# ESP-12.net
KiCad netlist of a schematic drawn in EAGLE
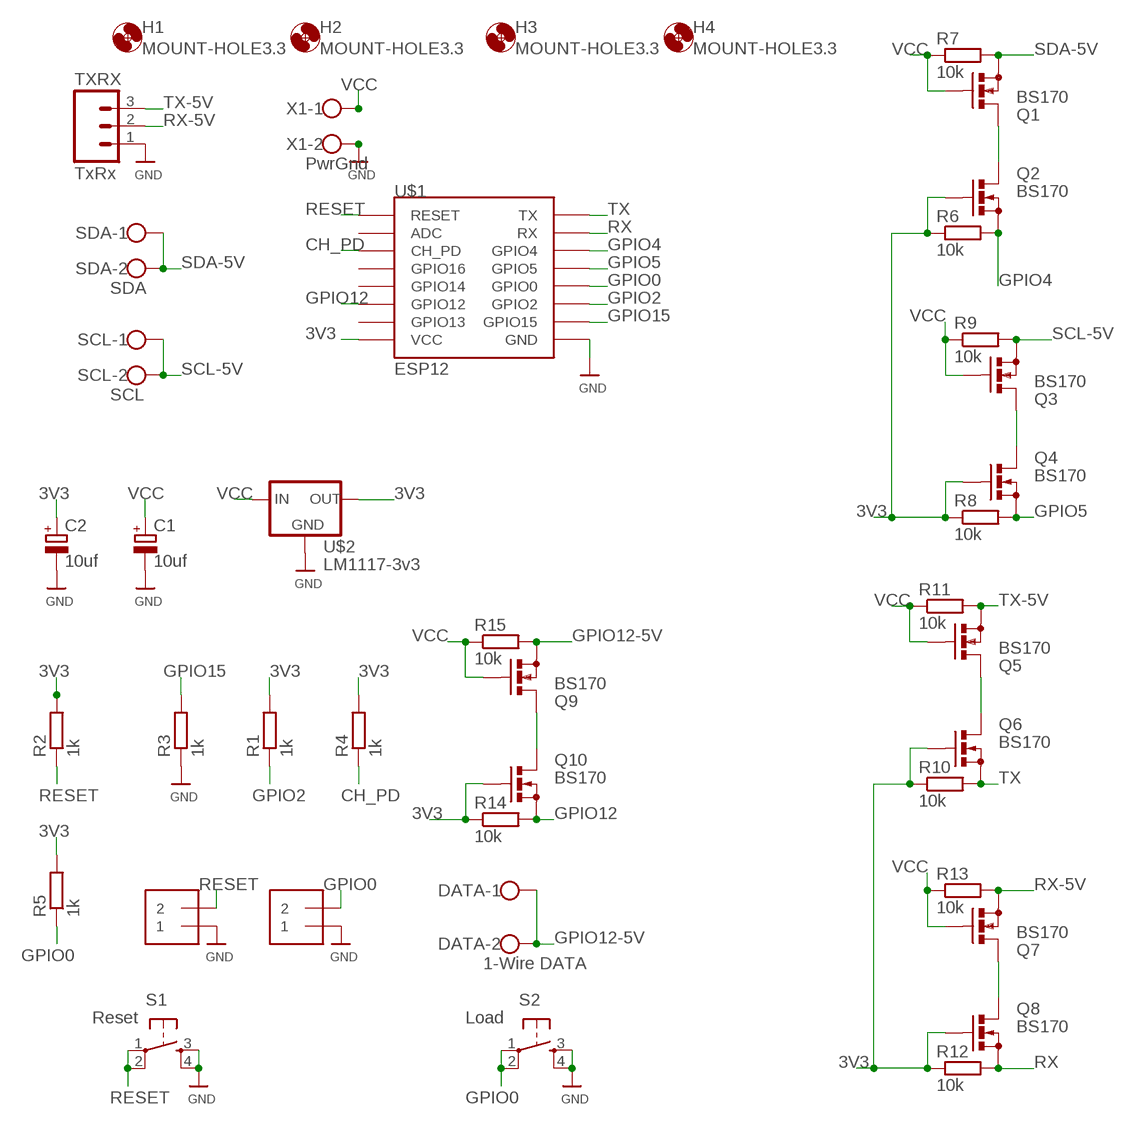
[diagram p0: schematic, sheet 1]

(export (version "E")
  (design (tool "Eeschema 10.0.6"))
  (components
    (comp (ref "C1")
      (value "10uf")
      (footprint "eagle-import:E5-4")
      (libsource (lib "eagle-import") (part "CPOL-EUE5-4"))
    )
    (comp (ref "C2")
      (value "10uf")
      (footprint "eagle-import:E5-4")
      (libsource (lib "eagle-import") (part "CPOL-EUE5-4"))
    )
    (comp (ref "DATA")
      (value "1-Wire DATA")
      (footprint "eagle-import:W237-102")
      (fields (field (name "MPN") "237-102"))
      (libsource (lib "eagle-import") (part "W237-102"))
    )
    (comp (ref "H1")
      (value "MOUNT-HOLE3.3")
      (footprint "eagle-import:3,3")
      (libsource (lib "eagle-import") (part "MOUNT-HOLE3.3"))
    )
    (comp (ref "H2")
      (value "MOUNT-HOLE3.3")
      (footprint "eagle-import:3,3")
      (libsource (lib "eagle-import") (part "MOUNT-HOLE3.3"))
    )
    (comp (ref "H3")
      (value "MOUNT-HOLE3.3")
      (footprint "eagle-import:3,3")
      (libsource (lib "eagle-import") (part "MOUNT-HOLE3.3"))
    )
    (comp (ref "H4")
      (value "MOUNT-HOLE3.3")
      (footprint "eagle-import:3,3")
      (libsource (lib "eagle-import") (part "MOUNT-HOLE3.3"))
    )
    (comp (ref "J1")
      (value "1X2-3.5MM")
      (footprint "eagle-import:1X2-3.5MM")
      (libsource (lib "eagle-import") (part "1X2-3.5MM"))
    )
    (comp (ref "J2")
      (value "1X2-3.5MM")
      (footprint "eagle-import:1X2-3.5MM")
      (libsource (lib "eagle-import") (part "1X2-3.5MM"))
    )
    (comp (ref "Q1")
      (value "BS170")
      (footprint "eagle-import:SOT54E")
      (libsource (lib "eagle-import") (part "BS170"))
    )
    (comp (ref "Q2")
      (value "BS170")
      (footprint "eagle-import:SOT54E")
      (libsource (lib "eagle-import") (part "BS170"))
    )
    (comp (ref "Q3")
      (value "BS170")
      (footprint "eagle-import:SOT54E")
      (libsource (lib "eagle-import") (part "BS170"))
    )
    (comp (ref "Q4")
      (value "BS170")
      (footprint "eagle-import:SOT54E")
      (libsource (lib "eagle-import") (part "BS170"))
    )
    (comp (ref "Q5")
      (value "BS170")
      (footprint "eagle-import:SOT54E")
      (libsource (lib "eagle-import") (part "BS170"))
    )
    (comp (ref "Q6")
      (value "BS170")
      (footprint "eagle-import:SOT54E")
      (libsource (lib "eagle-import") (part "BS170"))
    )
    (comp (ref "Q7")
      (value "BS170")
      (footprint "eagle-import:SOT54E")
      (libsource (lib "eagle-import") (part "BS170"))
    )
    (comp (ref "Q8")
      (value "BS170")
      (footprint "eagle-import:SOT54E")
      (libsource (lib "eagle-import") (part "BS170"))
    )
    (comp (ref "Q9")
      (value "BS170")
      (footprint "eagle-import:SOT54E")
      (libsource (lib "eagle-import") (part "BS170"))
    )
    (comp (ref "Q10")
      (value "BS170")
      (footprint "eagle-import:SOT54E")
      (libsource (lib "eagle-import") (part "BS170"))
    )
    (comp (ref "R1")
      (value "1k")
      (footprint "eagle-import:0207_10")
      (libsource (lib "eagle-import") (part "R-EU_0207/10"))
    )
    (comp (ref "R2")
      (value "1k")
      (footprint "eagle-import:0207_10")
      (libsource (lib "eagle-import") (part "R-EU_0207/10"))
    )
    (comp (ref "R3")
      (value "1k")
      (footprint "eagle-import:0207_10")
      (libsource (lib "eagle-import") (part "R-EU_0207/10"))
    )
    (comp (ref "R4")
      (value "1k")
      (footprint "eagle-import:0207_10")
      (libsource (lib "eagle-import") (part "R-EU_0207/10"))
    )
    (comp (ref "R5")
      (value "1k")
      (footprint "eagle-import:0207_10")
      (libsource (lib "eagle-import") (part "R-EU_0207/10"))
    )
    (comp (ref "R6")
      (value "10k")
      (footprint "eagle-import:0207_10")
      (libsource (lib "eagle-import") (part "R-EU_0207/10"))
    )
    (comp (ref "R7")
      (value "10k")
      (footprint "eagle-import:0207_10")
      (libsource (lib "eagle-import") (part "R-EU_0207/10"))
    )
    (comp (ref "R8")
      (value "10k")
      (footprint "eagle-import:0207_10")
      (libsource (lib "eagle-import") (part "R-EU_0207/10"))
    )
    (comp (ref "R9")
      (value "10k")
      (footprint "eagle-import:0207_10")
      (libsource (lib "eagle-import") (part "R-EU_0207/10"))
    )
    (comp (ref "R10")
      (value "10k")
      (footprint "eagle-import:0207_10")
      (libsource (lib "eagle-import") (part "R-EU_0207/10"))
    )
    (comp (ref "R11")
      (value "10k")
      (footprint "eagle-import:0207_10")
      (libsource (lib "eagle-import") (part "R-EU_0207/10"))
    )
    (comp (ref "R12")
      (value "10k")
      (footprint "eagle-import:0207_10")
      (libsource (lib "eagle-import") (part "R-EU_0207/10"))
    )
    (comp (ref "R13")
      (value "10k")
      (footprint "eagle-import:0207_10")
      (libsource (lib "eagle-import") (part "R-EU_0207/10"))
    )
    (comp (ref "R14")
      (value "10k")
      (footprint "eagle-import:0207_10")
      (libsource (lib "eagle-import") (part "R-EU_0207/10"))
    )
    (comp (ref "R15")
      (value "10k")
      (footprint "eagle-import:0207_10")
      (libsource (lib "eagle-import") (part "R-EU_0207/10"))
    )
    (comp (ref "S1")
      (value "Reset")
      (footprint "eagle-import:TACTILE-PTH")
      (libsource (lib "eagle-import") (part "TAC_SWITCHPTH"))
    )
    (comp (ref "S2")
      (value "Load")
      (footprint "eagle-import:TACTILE-PTH")
      (libsource (lib "eagle-import") (part "TAC_SWITCHPTH"))
    )
    (comp (ref "SCL")
      (value "SCL")
      (footprint "eagle-import:W237-102")
      (fields (field (name "MPN") "237-102"))
      (libsource (lib "eagle-import") (part "W237-102"))
    )
    (comp (ref "SDA")
      (value "SDA")
      (footprint "eagle-import:W237-102")
      (fields (field (name "MPN") "237-102"))
      (libsource (lib "eagle-import") (part "W237-102"))
    )
    (comp (ref "TXRX")
      (value "TxRx")
      (footprint "eagle-import:1X03_LONGPADS")
      (libsource (lib "eagle-import") (part "M03LONGPADS"))
    )
    (comp (ref "U$1")
      (value "ESP12")
      (footprint "eagle-import:ESP12")
      (libsource (lib "eagle-import") (part "ESP12"))
    )
    (comp (ref "U$2")
      (value "LM1117-3v3")
      (footprint "eagle-import:78XXL")
      (libsource (lib "eagle-import") (part "V_REG_LD1117VXX"))
    )
    (comp (ref "X1")
      (value "PwrGnd")
      (footprint "eagle-import:W237-102")
      (fields (field (name "MPN") "237-102"))
      (libsource (lib "eagle-import") (part "W237-102"))
    )
  )
  (nets
    (net (code "1") (name "/3V3") (class "Default")
      (node (ref "C2") (pin "+") (pinfunction "+_+") (pintype "passive"))
      (node (ref "Q10") (pin "G") (pinfunction "G_G") (pintype "passive"))
      (node (ref "Q2") (pin "G") (pinfunction "G_G") (pintype "passive"))
      (node (ref "Q4") (pin "G") (pinfunction "G_G") (pintype "passive"))
      (node (ref "Q6") (pin "G") (pinfunction "G_G") (pintype "passive"))
      (node (ref "Q8") (pin "G") (pinfunction "G_G") (pintype "passive"))
      (node (ref "R1") (pin "2") (pinfunction "2_2") (pintype "passive"))
      (node (ref "R10") (pin "1") (pinfunction "1_1") (pintype "passive"))
      (node (ref "R12") (pin "1") (pinfunction "1_1") (pintype "passive"))
      (node (ref "R14") (pin "1") (pinfunction "1_1") (pintype "passive"))
      (node (ref "R2") (pin "2") (pinfunction "2_2") (pintype "passive"))
      (node (ref "R4") (pin "2") (pinfunction "2_2") (pintype "passive"))
      (node (ref "R5") (pin "2") (pinfunction "2_2") (pintype "passive"))
      (node (ref "R6") (pin "1") (pinfunction "1_1") (pintype "passive"))
      (node (ref "R8") (pin "1") (pinfunction "1_1") (pintype "passive"))
      (node (ref "U$1") (pin "VCC") (pinfunction "VCC_VCC") (pintype "bidirectional"))
      (node (ref "U$2") (pin "GND") (pinfunction "OUT_GND") (pintype "output"))
    )
    (net (code "2") (name "/CH_PD") (class "Default")
      (node (ref "R4") (pin "1") (pinfunction "1_1") (pintype "passive"))
      (node (ref "U$1") (pin "CH_PD") (pinfunction "CH_PD_CH_PD") (pintype "bidirectional"))
    )
    (net (code "3") (name "/GPIO0") (class "Default")
      (node (ref "J2") (pin "2") (pinfunction "2_2") (pintype "passive"))
      (node (ref "R5") (pin "1") (pinfunction "1_1") (pintype "passive"))
      (node (ref "S2") (pin "1") (pinfunction "1_1") (pintype "passive"))
      (node (ref "S2") (pin "2") (pinfunction "2_2") (pintype "passive"))
      (node (ref "U$1") (pin "GPIO0") (pinfunction "GPIO0_GPIO0") (pintype "bidirectional"))
    )
    (net (code "4") (name "/GPIO2") (class "Default")
      (node (ref "R1") (pin "1") (pinfunction "1_1") (pintype "passive"))
      (node (ref "U$1") (pin "GPIO2") (pinfunction "GPIO2_GPIO2") (pintype "bidirectional"))
    )
    (net (code "5") (name "/GPIO4") (class "Default")
      (node (ref "Q2") (pin "S") (pinfunction "S_S") (pintype "passive"))
      (node (ref "R6") (pin "2") (pinfunction "2_2") (pintype "passive"))
      (node (ref "U$1") (pin "GPIO4") (pinfunction "GPIO4_GPIO4") (pintype "bidirectional"))
    )
    (net (code "6") (name "/GPIO5") (class "Default")
      (node (ref "Q4") (pin "S") (pinfunction "S_S") (pintype "passive"))
      (node (ref "R8") (pin "2") (pinfunction "2_2") (pintype "passive"))
      (node (ref "U$1") (pin "GPIO5") (pinfunction "GPIO5_GPIO5") (pintype "bidirectional"))
    )
    (net (code "7") (name "/GPIO12") (class "Default")
      (node (ref "Q10") (pin "S") (pinfunction "S_S") (pintype "passive"))
      (node (ref "R14") (pin "2") (pinfunction "2_2") (pintype "passive"))
      (node (ref "U$1") (pin "GPIO12") (pinfunction "GPIO12_GPIO12") (pintype "bidirectional"))
    )
    (net (code "8") (name "/GPIO12-5V") (class "Default")
      (node (ref "DATA") (pin "1") (pinfunction "KL_1") (pintype "passive"))
      (node (ref "DATA") (pin "2") (pinfunction "KL_2") (pintype "passive"))
      (node (ref "Q9") (pin "S") (pinfunction "S_S") (pintype "passive"))
      (node (ref "R15") (pin "2") (pinfunction "2_2") (pintype "passive"))
    )
    (net (code "9") (name "/GPIO15") (class "Default")
      (node (ref "R3") (pin "2") (pinfunction "2_2") (pintype "passive"))
      (node (ref "U$1") (pin "GPIO15") (pinfunction "GPIO15_GPIO15") (pintype "bidirectional"))
    )
    (net (code "10") (name "/RESET") (class "Default")
      (node (ref "J1") (pin "2") (pinfunction "2_2") (pintype "passive"))
      (node (ref "R2") (pin "1") (pinfunction "1_1") (pintype "passive"))
      (node (ref "S1") (pin "1") (pinfunction "1_1") (pintype "passive"))
      (node (ref "S1") (pin "2") (pinfunction "2_2") (pintype "passive"))
      (node (ref "U$1") (pin "RESET") (pinfunction "RESET_RESET") (pintype "bidirectional"))
    )
    (net (code "11") (name "/RX") (class "Default")
      (node (ref "Q8") (pin "S") (pinfunction "S_S") (pintype "passive"))
      (node (ref "R12") (pin "2") (pinfunction "2_2") (pintype "passive"))
      (node (ref "U$1") (pin "RX") (pinfunction "RX_RX") (pintype "bidirectional"))
    )
    (net (code "12") (name "/RX-5V") (class "Default")
      (node (ref "Q7") (pin "S") (pinfunction "S_S") (pintype "passive"))
      (node (ref "R13") (pin "2") (pinfunction "2_2") (pintype "passive"))
      (node (ref "TXRX") (pin "2") (pinfunction "2_2") (pintype "passive"))
    )
    (net (code "13") (name "/SCL-5V") (class "Default")
      (node (ref "Q3") (pin "S") (pinfunction "S_S") (pintype "passive"))
      (node (ref "R9") (pin "2") (pinfunction "2_2") (pintype "passive"))
      (node (ref "SCL") (pin "1") (pinfunction "KL_1") (pintype "passive"))
      (node (ref "SCL") (pin "2") (pinfunction "KL_2") (pintype "passive"))
    )
    (net (code "14") (name "/SDA-5V") (class "Default")
      (node (ref "Q1") (pin "S") (pinfunction "S_S") (pintype "passive"))
      (node (ref "R7") (pin "2") (pinfunction "2_2") (pintype "passive"))
      (node (ref "SDA") (pin "1") (pinfunction "KL_1") (pintype "passive"))
      (node (ref "SDA") (pin "2") (pinfunction "KL_2") (pintype "passive"))
    )
    (net (code "15") (name "/TX") (class "Default")
      (node (ref "Q6") (pin "S") (pinfunction "S_S") (pintype "passive"))
      (node (ref "R10") (pin "2") (pinfunction "2_2") (pintype "passive"))
      (node (ref "U$1") (pin "TX") (pinfunction "TX_TX") (pintype "bidirectional"))
    )
    (net (code "16") (name "/TX-5V") (class "Default")
      (node (ref "Q5") (pin "S") (pinfunction "S_S") (pintype "passive"))
      (node (ref "R11") (pin "2") (pinfunction "2_2") (pintype "passive"))
      (node (ref "TXRX") (pin "3") (pinfunction "3_3") (pintype "passive"))
    )
    (net (code "17") (name "/VCC") (class "Default")
      (node (ref "C1") (pin "+") (pinfunction "+_+") (pintype "passive"))
      (node (ref "Q1") (pin "G") (pinfunction "G_G") (pintype "passive"))
      (node (ref "Q3") (pin "G") (pinfunction "G_G") (pintype "passive"))
      (node (ref "Q5") (pin "G") (pinfunction "G_G") (pintype "passive"))
      (node (ref "Q7") (pin "G") (pinfunction "G_G") (pintype "passive"))
      (node (ref "Q9") (pin "G") (pinfunction "G_G") (pintype "passive"))
      (node (ref "R11") (pin "1") (pinfunction "1_1") (pintype "passive"))
      (node (ref "R13") (pin "1") (pinfunction "1_1") (pintype "passive"))
      (node (ref "R15") (pin "1") (pinfunction "1_1") (pintype "passive"))
      (node (ref "R7") (pin "1") (pinfunction "1_1") (pintype "passive"))
      (node (ref "R9") (pin "1") (pinfunction "1_1") (pintype "passive"))
      (node (ref "U$2") (pin "OUT") (pinfunction "IN_OUT") (pintype "input"))
      (node (ref "X1") (pin "1") (pinfunction "KL_1") (pintype "passive"))
    )
    (net (code "18") (name "GND") (class "Default")
      (node (ref "C1") (pin "-") (pinfunction "-_-") (pintype "passive"))
      (node (ref "C2") (pin "-") (pinfunction "-_-") (pintype "passive"))
      (node (ref "J1") (pin "1") (pinfunction "1_1") (pintype "passive"))
      (node (ref "J2") (pin "1") (pinfunction "1_1") (pintype "passive"))
      (node (ref "R3") (pin "1") (pinfunction "1_1") (pintype "passive"))
      (node (ref "S1") (pin "3") (pinfunction "3_3") (pintype "passive"))
      (node (ref "S1") (pin "4") (pinfunction "4_4") (pintype "passive"))
      (node (ref "S2") (pin "3") (pinfunction "3_3") (pintype "passive"))
      (node (ref "S2") (pin "4") (pinfunction "4_4") (pintype "passive"))
      (node (ref "TXRX") (pin "1") (pinfunction "1_1") (pintype "passive"))
      (node (ref "U$1") (pin "GND") (pinfunction "GND_GND") (pintype "bidirectional"))
      (node (ref "U$2") (pin "IN") (pinfunction "GND_IN") (pintype "input"))
      (node (ref "X1") (pin "2") (pinfunction "KL_2") (pintype "passive"))
    )
    (net (code "19") (name "Net-(Q1-PadD)") (class "Default")
      (node (ref "Q1") (pin "D") (pinfunction "D_D") (pintype "passive"))
      (node (ref "Q2") (pin "D") (pinfunction "D_D") (pintype "passive"))
    )
    (net (code "20") (name "Net-(Q3-PadD)") (class "Default")
      (node (ref "Q3") (pin "D") (pinfunction "D_D") (pintype "passive"))
      (node (ref "Q4") (pin "D") (pinfunction "D_D") (pintype "passive"))
    )
    (net (code "21") (name "Net-(Q5-PadD)") (class "Default")
      (node (ref "Q5") (pin "D") (pinfunction "D_D") (pintype "passive"))
      (node (ref "Q6") (pin "D") (pinfunction "D_D") (pintype "passive"))
    )
    (net (code "22") (name "Net-(Q7-PadD)") (class "Default")
      (node (ref "Q7") (pin "D") (pinfunction "D_D") (pintype "passive"))
      (node (ref "Q8") (pin "D") (pinfunction "D_D") (pintype "passive"))
    )
    (net (code "23") (name "Net-(Q10-PadD)") (class "Default")
      (node (ref "Q10") (pin "D") (pinfunction "D_D") (pintype "passive"))
      (node (ref "Q9") (pin "D") (pinfunction "D_D") (pintype "passive"))
    )
    (net (code "24") (name "unconnected-(U$1-PadADC)") (class "Default")
      (node (ref "U$1") (pin "ADC") (pinfunction "ADC_ADC") (pintype "bidirectional"))
    )
    (net (code "25") (name "unconnected-(U$1-PadGPIO13)") (class "Default")
      (node (ref "U$1") (pin "GPIO13") (pinfunction "GPIO13_GPIO13") (pintype "bidirectional"))
    )
    (net (code "26") (name "unconnected-(U$1-PadGPIO14)") (class "Default")
      (node (ref "U$1") (pin "GPIO14") (pinfunction "GPIO14_GPIO14") (pintype "bidirectional"))
    )
    (net (code "27") (name "unconnected-(U$1-PadGPIO16)") (class "Default")
      (node (ref "U$1") (pin "GPIO16") (pinfunction "GPIO16_GPIO16") (pintype "bidirectional"))
    )
  )
)
